# Sheet1.net
KiCad netlist of a schematic drawn in Altium Designer
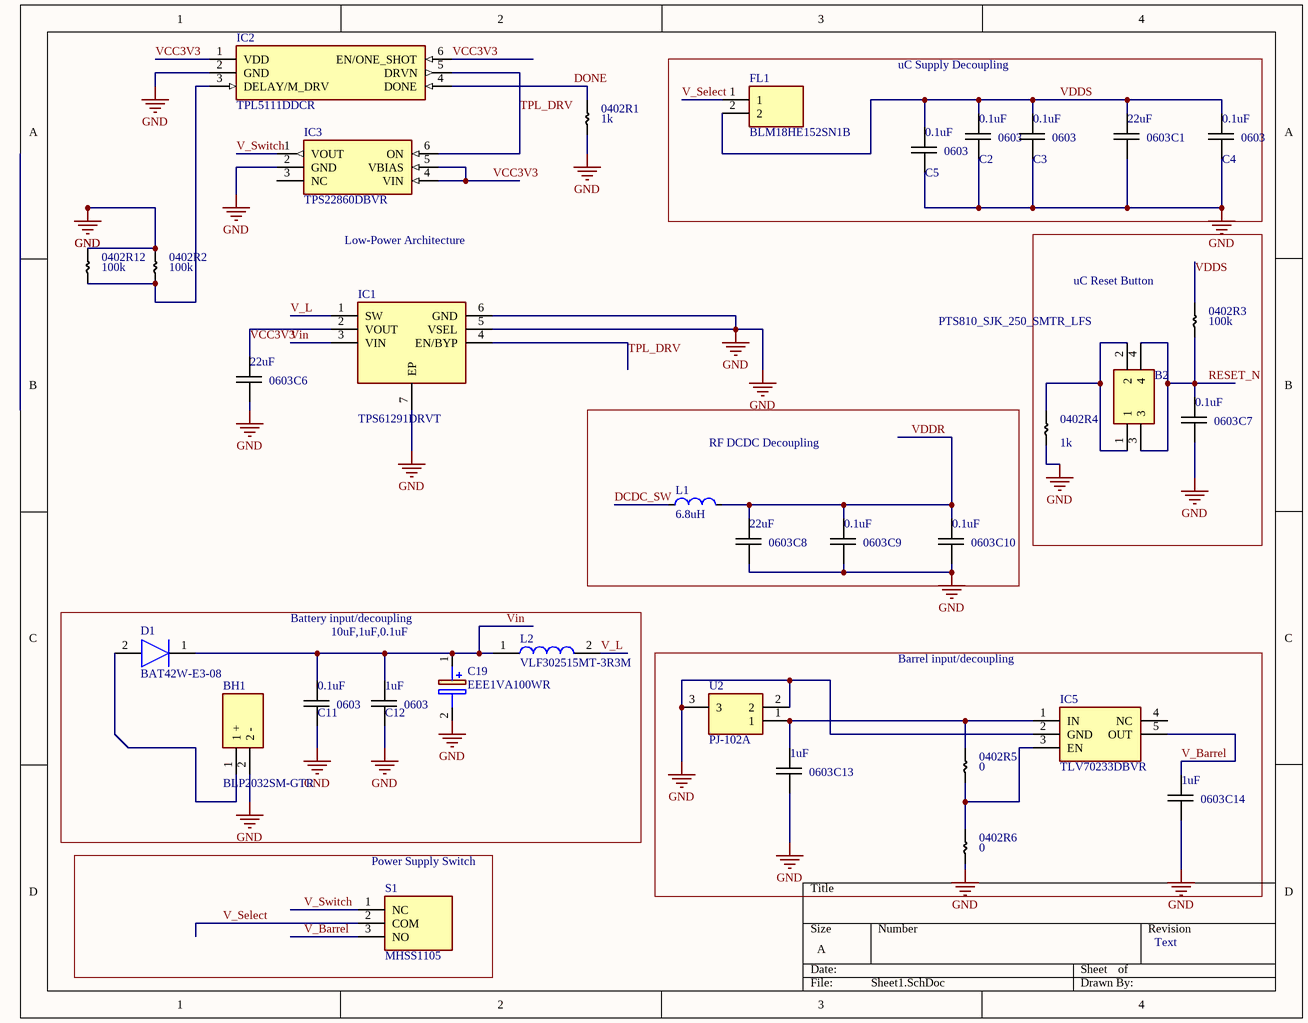
[diagram p0: Sheet1.SchDoc]

(export (version "E")
  (design (tool "Eeschema 10.0.6"))
  (components
    (comp (ref "B2")
      (value "PTS810_SJK_250_SMTR_LFS")
      (footprint "SamacSys:PTS810SJK250SMTRLFS")
      (description "Crystal or Oscillator")
      (fields
        (field (name "MANUFACTURER_PART_NUMBER") "PTS810 SJK 250 SMTR LFS")
        (field (name "MOUSER PART NUMBER") "611-PTS810SJK250SMTR")
      )
      (libsource (lib "*") (part "PTS810_SJK_250_SMTR_LFS"))
    )
    (comp (ref "BH1")
      (value "BLP2032SM-GTR")
      (footprint "BLP2032SMGTR")
      (description "Undefined or Miscellaneous")
      (libsource (lib "Enviornmental_Sensor") (part "BLP2032SM-GTR"))
    )
    (comp (ref "C1")
      (value "22uF")
      (footprint "0603_SMD")
      (libsource (lib "Enviornmental_Sensor") (part "C_0603"))
    )
    (comp (ref "C2")
      (value "0.1uF")
      (footprint "0603_SMD")
      (libsource (lib "Enviornmental_Sensor") (part "C_0603"))
    )
    (comp (ref "C3")
      (value "0.1uF")
      (footprint "0603_SMD")
      (libsource (lib "Enviornmental_Sensor") (part "C_0603"))
    )
    (comp (ref "C4")
      (value "0.1uF")
      (footprint "0603_SMD")
      (libsource (lib "Enviornmental_Sensor") (part "C_0603"))
    )
    (comp (ref "C5")
      (value "0.1uF")
      (footprint "0603_SMD")
      (libsource (lib "Enviornmental_Sensor") (part "C_0603"))
    )
    (comp (ref "C6")
      (value "22uF")
      (footprint "0603_SMD")
      (libsource (lib "Enviornmental_Sensor") (part "C_0603"))
    )
    (comp (ref "C7")
      (value "0.1uF")
      (footprint "0603_SMD")
      (libsource (lib "Enviornmental_Sensor") (part "C_0603"))
    )
    (comp (ref "C8")
      (value "22uF")
      (footprint "0603_SMD")
      (libsource (lib "Enviornmental_Sensor") (part "C_0603"))
    )
    (comp (ref "C9")
      (value "0.1uF")
      (footprint "0603_SMD")
      (libsource (lib "Enviornmental_Sensor") (part "C_0603"))
    )
    (comp (ref "C10")
      (value "0.1uF")
      (footprint "0603_SMD")
      (libsource (lib "Enviornmental_Sensor") (part "C_0603"))
    )
    (comp (ref "C11")
      (value "0.1uF")
      (footprint "0603_SMD")
      (libsource (lib "Enviornmental_Sensor") (part "C_0603"))
    )
    (comp (ref "C12")
      (value "1uF")
      (footprint "0603_SMD")
      (libsource (lib "Enviornmental_Sensor") (part "C_0603"))
    )
    (comp (ref "C13")
      (value "1uF")
      (footprint "0603_SMD")
      (libsource (lib "Enviornmental_Sensor") (part "C_0603"))
    )
    (comp (ref "C14")
      (value "1uF")
      (footprint "0603_SMD")
      (libsource (lib "Enviornmental_Sensor") (part "C_0603"))
    )
    (comp (ref "C19")
      (value "EEE1VA100WR")
      (footprint "SamacSys:CAPAE430X550N")
      (description "Capacitor Polarised")
      (fields (field (name "RS PART NUMBER") "1766382"))
      (libsource (lib "*") (part "EEE1VA100WR"))
    )
    (comp (ref "D1")
      (value "BAT42W-E3-08")
      (footprint "SamacSys:SOD3716X135N")
      (description "Diode")
      (fields
        (field (name "MOUSER PART NUMBER") "78-BAT42W-E3-08")
        (field (name "RS PART NUMBER") "1808601P")
      )
      (libsource (lib "*") (part "BAT42W-E3-08"))
    )
    (comp (ref "FL1")
      (value "BLM18HE152SN1B")
      (footprint "SamacSys:BEADC1608X95N")
      (description "Filter")
      (libsource (lib "*") (part "BLM18HE152SN1B"))
    )
    (comp (ref "IC1")
      (value "TPS61291DRVT")
      (footprint "SON65P200X200X80-7N")
      (description "Integrated Circuit")
      (fields
        (field (name "MOUSER PART NUMBER") "595-TPS61291DRVT")
        (field (name "RS PART NUMBER") "9143112P")
      )
      (libsource (lib "Enviornmental_Sensor") (part "TPS61291DRVT"))
    )
    (comp (ref "IC2")
      (value "TPL5111DDCR")
      (footprint "SOT95P280X110-6N")
      (description "Undefined or Miscellaneous")
      (fields (field (name "MOUSER PART NUMBER") "595-TPL5111DDCR"))
      (libsource (lib "Enviornmental_Sensor") (part "TPL5111DDCR"))
    )
    (comp (ref "IC3")
      (value "TPS22860DBVR")
      (footprint "SOT95P280X145-6N")
      (description "Switch")
      (fields (field (name "MOUSER PART NUMBER") "595-TPS22860DBVR"))
      (libsource (lib "Enviornmental_Sensor") (part "TPS22860DBVR"))
    )
    (comp (ref "IC5")
      (value "TLV70233DBVR")
      (footprint "SamacSys:SOT95P280X145-5N")
      (description "Integrated Circuit")
      (fields (field (name "MOUSER PART NUMBER") "595-TLV70233DBVR"))
      (libsource (lib "*") (part "TLV70233DBVR"))
    )
    (comp (ref "L1")
      (value "6.8uH")
      (footprint "PASSIVE-INDUCTOR-0603")
      (description "Generic Inductor")
      (fields (field (name "Comment") "Passive-Inductor (Generic)"))
      (libsource (lib "MasterLib") (part "Passive-Inductor (Generic)"))
    )
    (comp (ref "L2")
      (value "VLF302515MT-3R3M")
      (footprint "SamacSys:VLF302515MT")
      (description "Inductor")
      (fields (field (name "MOUSER PART NUMBER") "810-VLF302515MT-3R3M"))
      (libsource (lib "*") (part "VLF302515MT-3R3M"))
    )
    (comp (ref "R1")
      (value "1k")
      (footprint "0402_SMD")
      (libsource (lib "Enviornmental_Sensor") (part "R_0402"))
    )
    (comp (ref "R2")
      (value "100k")
      (footprint "0402_SMD")
      (libsource (lib "Enviornmental_Sensor") (part "R_0402"))
    )
    (comp (ref "R3")
      (value "100k")
      (footprint "0402_SMD")
      (libsource (lib "Enviornmental_Sensor") (part "R_0402"))
    )
    (comp (ref "R4")
      (value "1k")
      (footprint "0402_SMD")
      (libsource (lib "Enviornmental_Sensor") (part "R_0402"))
    )
    (comp (ref "R5")
      (value "0")
      (footprint "0402_SMD")
      (libsource (lib "Enviornmental_Sensor") (part "R_0402"))
    )
    (comp (ref "R6")
      (value "0")
      (footprint "0402_SMD")
      (libsource (lib "Enviornmental_Sensor") (part "R_0402"))
    )
    (comp (ref "R12")
      (value "100k")
      (footprint "0402_SMD")
      (libsource (lib "Enviornmental_Sensor") (part "R_0402"))
    )
    (comp (ref "S1")
      (value "MHSS1105")
      (footprint "MHSS1105")
      (description "Switch")
      (fields (field (name "MOUSER PART NUMBER") "642-MHSS1105"))
      (libsource (lib "Enviornmental_Sensor") (part "MHSS1105"))
    )
    (comp (ref "U2")
      (value "PJ-102A")
      (footprint "PJ-102AH")
      (description "Connector")
      (fields (field (name "MOUSER PART NUMBER") "490-PJ-102A"))
      (libsource (lib "Enviornmental_Sensor") (part "PJ-102A"))
    )
  )
  (nets
    (net (code "1") (name "/DCDC_SW") (class "Default")
      (node (ref "L1") (pin "1") (pinfunction "1_1") (pintype "passive"))
    )
    (net (code "2") (name "/DONE") (class "Default")
      (node (ref "IC2") (pin "4") (pinfunction "DONE_4") (pintype "input"))
      (node (ref "R1") (pin "1") (pinfunction "1_1") (pintype "passive"))
    )
    (net (code "3") (name "/RESET_N") (class "Default")
      (node (ref "B2") (pin "3") (pinfunction "3_3") (pintype "passive"))
      (node (ref "B2") (pin "4") (pinfunction "4_4") (pintype "passive"))
      (node (ref "C7") (pin "2") (pinfunction "2_2") (pintype "passive"))
      (node (ref "R3") (pin "2") (pinfunction "2_2") (pintype "passive"))
    )
    (net (code "4") (name "/TPL_DRV") (class "Default")
      (node (ref "IC1") (pin "4") (pinfunction "EN/BYP_4") (pintype "passive"))
      (node (ref "IC2") (pin "5") (pinfunction "DRVN_5") (pintype "output"))
      (node (ref "IC3") (pin "6") (pinfunction "ON_6") (pintype "input"))
    )
    (net (code "5") (name "/VCC3V3") (class "Default")
      (node (ref "C6") (pin "2") (pinfunction "2_2") (pintype "passive"))
      (node (ref "IC1") (pin "2") (pinfunction "VOUT_2") (pintype "passive"))
      (node (ref "IC2") (pin "1") (pinfunction "VDD_1") (pintype "power_in"))
      (node (ref "IC2") (pin "6") (pinfunction "EN/ONE_SHOT_6") (pintype "input"))
      (node (ref "IC3") (pin "4") (pinfunction "VIN_4") (pintype "input"))
      (node (ref "IC3") (pin "5") (pinfunction "VBIAS_5") (pintype "input"))
    )
    (net (code "6") (name "/VDDR") (class "Default")
      (node (ref "C10") (pin "2") (pinfunction "2_2") (pintype "passive"))
      (node (ref "C8") (pin "2") (pinfunction "2_2") (pintype "passive"))
      (node (ref "C9") (pin "2") (pinfunction "2_2") (pintype "passive"))
      (node (ref "L1") (pin "2") (pinfunction "2_2") (pintype "passive"))
    )
    (net (code "7") (name "/VDDS") (class "Default")
      (node (ref "C1") (pin "2") (pinfunction "2_2") (pintype "passive"))
      (node (ref "C2") (pin "2") (pinfunction "2_2") (pintype "passive"))
      (node (ref "C3") (pin "2") (pinfunction "2_2") (pintype "passive"))
      (node (ref "C4") (pin "2") (pinfunction "2_2") (pintype "passive"))
      (node (ref "C5") (pin "2") (pinfunction "2_2") (pintype "passive"))
      (node (ref "FL1") (pin "2") (pinfunction "2_2") (pintype "passive"))
      (node (ref "R3") (pin "1") (pinfunction "1_1") (pintype "passive"))
    )
    (net (code "8") (name "/V_Barrel") (class "Default")
      (node (ref "C14") (pin "2") (pinfunction "2_2") (pintype "passive"))
      (node (ref "IC5") (pin "5") (pinfunction "OUT_5") (pintype "passive"))
      (node (ref "S1") (pin "3") (pinfunction "NO_3") (pintype "passive"))
    )
    (net (code "9") (name "/V_L") (class "Default")
      (node (ref "IC1") (pin "1") (pinfunction "SW_1") (pintype "passive"))
      (node (ref "L2") (pin "2") (pinfunction "2_2") (pintype "passive"))
    )
    (net (code "10") (name "/V_Select") (class "Default")
      (node (ref "FL1") (pin "1") (pinfunction "1_1") (pintype "passive"))
      (node (ref "S1") (pin "2") (pinfunction "COM_2") (pintype "passive"))
    )
    (net (code "11") (name "/V_Switch") (class "Default")
      (node (ref "IC3") (pin "1") (pinfunction "VOUT_1") (pintype "output"))
      (node (ref "S1") (pin "1") (pinfunction "NC_1") (pintype "passive"))
    )
    (net (code "12") (name "/Vin") (class "Default")
      (node (ref "C11") (pin "2") (pinfunction "2_2") (pintype "passive"))
      (node (ref "C12") (pin "2") (pinfunction "2_2") (pintype "passive"))
      (node (ref "C19") (pin "1") (pinfunction "+_1") (pintype "passive"))
      (node (ref "D1") (pin "1") (pinfunction "K_1") (pintype "passive"))
      (node (ref "IC1") (pin "3") (pinfunction "VIN_3") (pintype "passive"))
      (node (ref "L2") (pin "1") (pinfunction "1_1") (pintype "passive"))
    )
    (net (code "13") (name "GND") (class "Default")
      (node (ref "BH1") (pin "2") (pinfunction "2_-_2") (pintype "passive"))
      (node (ref "C1") (pin "1") (pinfunction "1_1") (pintype "passive"))
      (node (ref "C10") (pin "1") (pinfunction "1_1") (pintype "passive"))
      (node (ref "C11") (pin "1") (pinfunction "1_1") (pintype "passive"))
      (node (ref "C12") (pin "1") (pinfunction "1_1") (pintype "passive"))
      (node (ref "C13") (pin "1") (pinfunction "1_1") (pintype "passive"))
      (node (ref "C14") (pin "1") (pinfunction "1_1") (pintype "passive"))
      (node (ref "C19") (pin "2") (pinfunction "-_2") (pintype "passive"))
      (node (ref "C2") (pin "1") (pinfunction "1_1") (pintype "passive"))
      (node (ref "C3") (pin "1") (pinfunction "1_1") (pintype "passive"))
      (node (ref "C4") (pin "1") (pinfunction "1_1") (pintype "passive"))
      (node (ref "C5") (pin "1") (pinfunction "1_1") (pintype "passive"))
      (node (ref "C6") (pin "1") (pinfunction "1_1") (pintype "passive"))
      (node (ref "C7") (pin "1") (pinfunction "1_1") (pintype "passive"))
      (node (ref "C8") (pin "1") (pinfunction "1_1") (pintype "passive"))
      (node (ref "C9") (pin "1") (pinfunction "1_1") (pintype "passive"))
      (node (ref "IC1") (pin "5") (pinfunction "VSEL_5") (pintype "passive"))
      (node (ref "IC1") (pin "6") (pinfunction "GND_6") (pintype "passive"))
      (node (ref "IC1") (pin "7") (pinfunction "EP_7") (pintype "passive"))
      (node (ref "IC2") (pin "2") (pinfunction "GND_2") (pintype "power_in"))
      (node (ref "IC3") (pin "2") (pinfunction "GND_2") (pintype "power_in"))
      (node (ref "IC5") (pin "2") (pinfunction "GND_2") (pintype "passive"))
      (node (ref "R1") (pin "2") (pinfunction "2_2") (pintype "passive"))
      (node (ref "R12") (pin "1") (pinfunction "1_1") (pintype "passive"))
      (node (ref "R2") (pin "1") (pinfunction "1_1") (pintype "passive"))
      (node (ref "R4") (pin "2") (pinfunction "2_2") (pintype "passive"))
      (node (ref "R6") (pin "2") (pinfunction "2_2") (pintype "passive"))
      (node (ref "U2") (pin "2") (pinfunction "2_2") (pintype "passive"))
      (node (ref "U2") (pin "3") (pinfunction "3_3") (pintype "passive"))
    )
    (net (code "14") (name "Net-(B2-Pad1)") (class "Default")
      (node (ref "B2") (pin "1") (pinfunction "1_1") (pintype "passive"))
      (node (ref "B2") (pin "2") (pinfunction "2_2") (pintype "passive"))
      (node (ref "R4") (pin "1") (pinfunction "1_1") (pintype "passive"))
    )
    (net (code "15") (name "Net-(BH1-1_+)") (class "Default")
      (node (ref "BH1") (pin "1") (pinfunction "1_+_1") (pintype "passive"))
      (node (ref "D1") (pin "2") (pinfunction "A_2") (pintype "passive"))
    )
    (net (code "16") (name "Net-(IC2-DELAY{slash}M_DRV)") (class "Default")
      (node (ref "IC2") (pin "3") (pinfunction "DELAY/M_DRV_3") (pintype "input"))
      (node (ref "R12") (pin "2") (pinfunction "2_2") (pintype "passive"))
      (node (ref "R2") (pin "2") (pinfunction "2_2") (pintype "passive"))
    )
    (net (code "17") (name "Net-(IC5-EN)") (class "Default")
      (node (ref "IC5") (pin "3") (pinfunction "EN_3") (pintype "passive"))
      (node (ref "R5") (pin "2") (pinfunction "2_2") (pintype "passive"))
      (node (ref "R6") (pin "1") (pinfunction "1_1") (pintype "passive"))
    )
    (net (code "18") (name "Net-(IC5-IN)") (class "Default")
      (node (ref "C13") (pin "2") (pinfunction "2_2") (pintype "passive"))
      (node (ref "IC5") (pin "1") (pinfunction "IN_1") (pintype "passive"))
      (node (ref "R5") (pin "1") (pinfunction "1_1") (pintype "passive"))
      (node (ref "U2") (pin "1") (pinfunction "1_1") (pintype "passive"))
    )
    (net (code "19") (name "unconnected-(IC3-NC-Pad3)") (class "Default")
      (node (ref "IC3") (pin "3") (pinfunction "NC_3") (pintype "passive"))
    )
    (net (code "20") (name "unconnected-(IC5-NC-Pad4)") (class "Default")
      (node (ref "IC5") (pin "4") (pinfunction "NC_4") (pintype "passive"))
    )
  )
)
